# 555.net
KiCad netlist of a schematic drawn in EAGLE
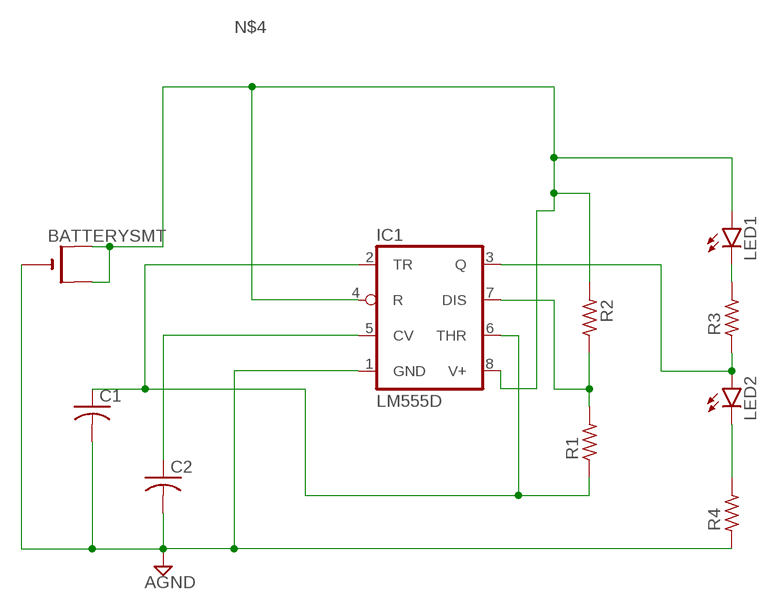
[diagram p0: schematic, sheet 1]

(export (version "E")
  (design (tool "Eeschema 10.0.6"))
  (components
    (comp (ref "BATTERYSMT")
      (value "CR1220SMT")
      (footprint "eagle-import:CR1220-SMD")
      (libsource (lib "eagle-import") (part "CR1220SMT"))
    )
    (comp (ref "C1")
      (value "C-USC0805")
      (footprint "eagle-import:C0805")
      (libsource (lib "eagle-import") (part "C-USC0805"))
    )
    (comp (ref "C2")
      (value "C-USC0805")
      (footprint "eagle-import:C0805")
      (libsource (lib "eagle-import") (part "C-USC0805"))
    )
    (comp (ref "IC1")
      (value "LM555D")
      (footprint "eagle-import:SO08")
      (libsource (lib "eagle-import") (part "555DLM"))
    )
    (comp (ref "LED1")
      (value "LEDCHIP-LED0805")
      (footprint "eagle-import:CHIP-LED0805")
      (libsource (lib "eagle-import") (part "LEDCHIP-LED0805"))
    )
    (comp (ref "LED2")
      (value "LEDCHIP-LED0805")
      (footprint "eagle-import:CHIP-LED0805")
      (libsource (lib "eagle-import") (part "LEDCHIP-LED0805"))
    )
    (comp (ref "R1")
      (value "R_0805")
      (footprint "eagle-import:R0805")
      (libsource (lib "eagle-import") (part "R_0805"))
    )
    (comp (ref "R2")
      (value "R_0805")
      (footprint "eagle-import:R0805")
      (libsource (lib "eagle-import") (part "R_0805"))
    )
    (comp (ref "R3")
      (value "R_0805")
      (footprint "eagle-import:R0805")
      (libsource (lib "eagle-import") (part "R_0805"))
    )
    (comp (ref "R4")
      (value "R_0805")
      (footprint "eagle-import:R0805")
      (libsource (lib "eagle-import") (part "R_0805"))
    )
  )
  (nets
    (net (code "1") (name "/N$4") (class "Default")
      (node (ref "BATTERYSMT") (pin "+$1") (pinfunction "+_+$1") (pintype "passive"))
      (node (ref "BATTERYSMT") (pin "+$2") (pinfunction "+1_+$2") (pintype "passive"))
      (node (ref "IC1") (pin "4") (pinfunction "R_4") (pintype "input"))
      (node (ref "IC1") (pin "8") (pinfunction "V+_8") (pintype "power_in"))
      (node (ref "LED1") (pin "A") (pinfunction "A_A") (pintype "passive"))
      (node (ref "R2") (pin "1") (pinfunction "1_1") (pintype "passive"))
    )
    (net (code "2") (name "AGND") (class "Default")
      (node (ref "BATTERYSMT") (pin "-") (pinfunction "-_-") (pintype "passive"))
      (node (ref "C1") (pin "2") (pinfunction "2_2") (pintype "passive"))
      (node (ref "C2") (pin "2") (pinfunction "2_2") (pintype "passive"))
      (node (ref "IC1") (pin "1") (pinfunction "GND_1") (pintype "power_in"))
      (node (ref "R4") (pin "1") (pinfunction "1_1") (pintype "passive"))
    )
    (net (code "3") (name "Net-(IC1-CV)") (class "Default")
      (node (ref "C2") (pin "1") (pinfunction "1_1") (pintype "passive"))
      (node (ref "IC1") (pin "5") (pinfunction "CV_5") (pintype "input"))
    )
    (net (code "4") (name "Net-(IC1-DIS)") (class "Default")
      (node (ref "IC1") (pin "7") (pinfunction "DIS_7") (pintype "input"))
      (node (ref "R1") (pin "2") (pinfunction "2_2") (pintype "passive"))
      (node (ref "R2") (pin "2") (pinfunction "2_2") (pintype "passive"))
    )
    (net (code "5") (name "Net-(IC1-Q)") (class "Default")
      (node (ref "IC1") (pin "3") (pinfunction "Q_3") (pintype "output"))
      (node (ref "LED2") (pin "A") (pinfunction "A_A") (pintype "passive"))
      (node (ref "R3") (pin "1") (pinfunction "1_1") (pintype "passive"))
    )
    (net (code "6") (name "Net-(IC1-THR)") (class "Default")
      (node (ref "C1") (pin "1") (pinfunction "1_1") (pintype "passive"))
      (node (ref "IC1") (pin "2") (pinfunction "TR_2") (pintype "input"))
      (node (ref "IC1") (pin "6") (pinfunction "THR_6") (pintype "input"))
      (node (ref "R1") (pin "1") (pinfunction "1_1") (pintype "passive"))
    )
    (net (code "7") (name "Net-(LED1-PadC)") (class "Default")
      (node (ref "LED1") (pin "C") (pinfunction "C_C") (pintype "passive"))
      (node (ref "R3") (pin "2") (pinfunction "2_2") (pintype "passive"))
    )
    (net (code "8") (name "Net-(LED2-PadC)") (class "Default")
      (node (ref "LED2") (pin "C") (pinfunction "C_C") (pintype "passive"))
      (node (ref "R4") (pin "2") (pinfunction "2_2") (pintype "passive"))
    )
  )
)
